# GPS_and_Telemetry.net
KiCad netlist of a schematic drawn in Altium Designer
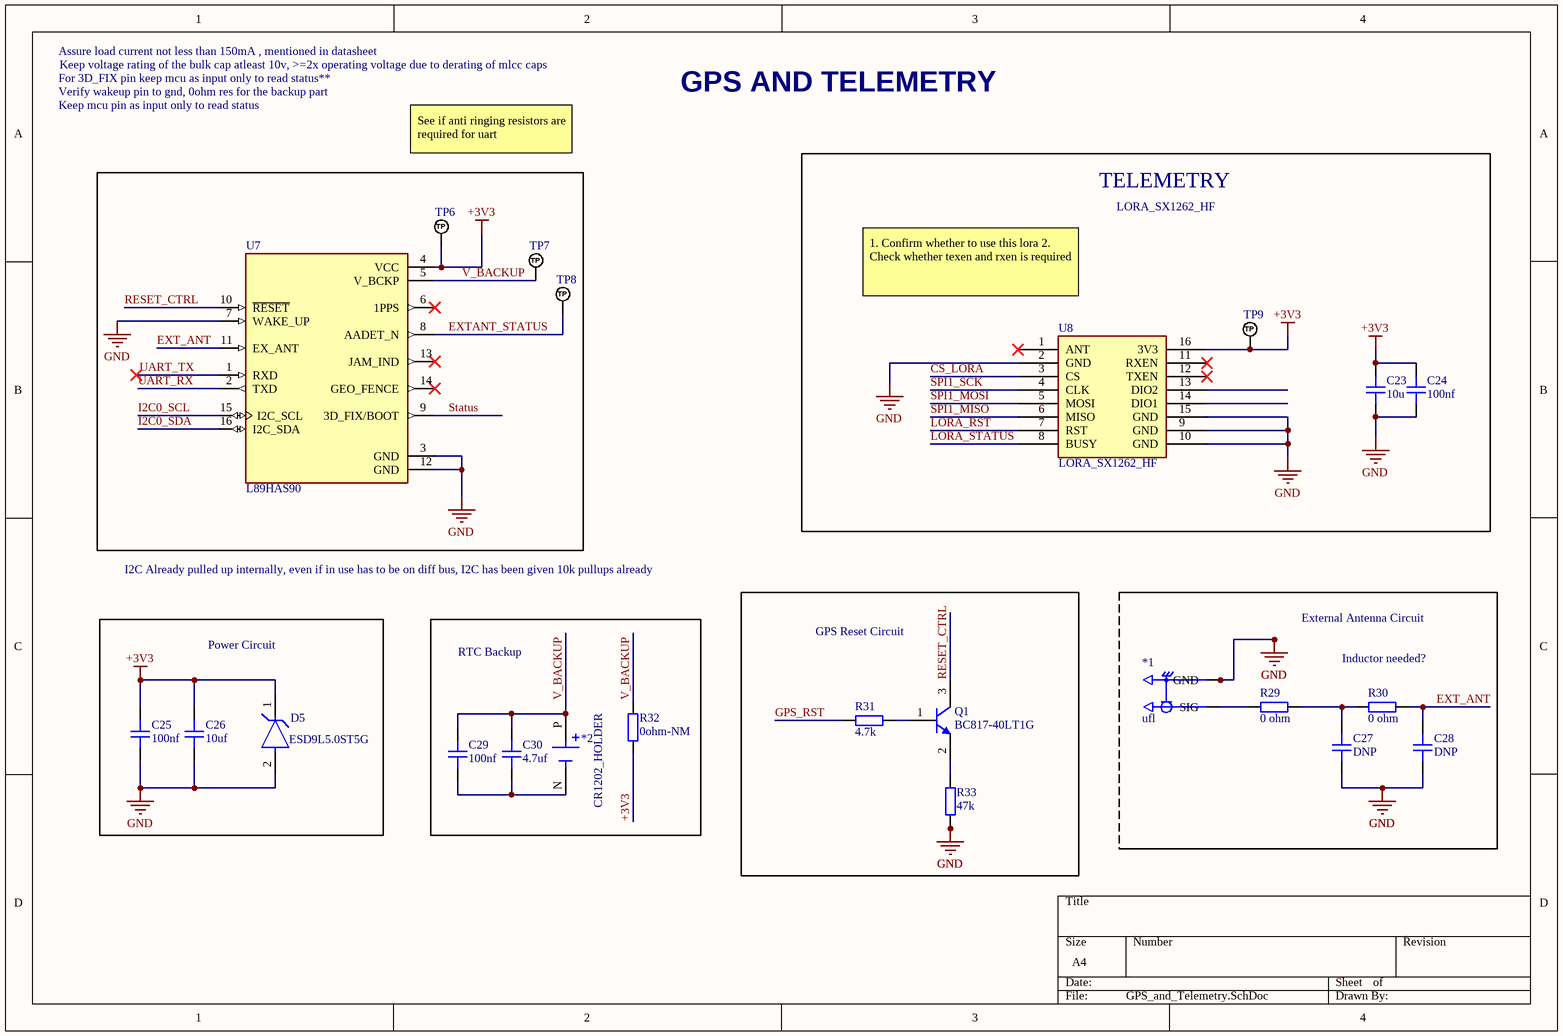
[diagram p0: GPS_and_Telemetry.SchDoc]

(export (version "E")
  (design (tool "Eeschema 10.0.6"))
  (components
    (comp (ref "*1") (value "ufl") (footprint "UFL") (libsource (lib "SchematicSchlib1") (part "ufl")))
    (comp (ref "*2")
      (value "CR1202_HOLDER")
      (footprint "CR1220_CELL_HOLDER")
      (libsource (lib "SchematicSchlib1") (part "CR1202_HOLDER"))
    )
    (comp (ref "C23")
      (value "10u")
      (footprint "CAP_0805")
      (description "Capacitor SMD 0805")
      (libsource (lib "SchematicSchlib1") (part "CAP_0805"))
    )
    (comp (ref "C24")
      (value "100nf")
      (footprint "CAP_0402")
      (description "Capacitor SMD 0402")
      (libsource (lib "SchematicSchlib1") (part "CAP_0402"))
    )
    (comp (ref "C25")
      (value "100nf")
      (footprint "CAP_0402")
      (description "Capacitor SMD 0402")
      (libsource (lib "SchematicSchlib1") (part "CAP_0402"))
    )
    (comp (ref "C26")
      (value "10uf")
      (footprint "CAP_0805")
      (description "Capacitor SMD 0805")
      (libsource (lib "SchematicSchlib1") (part "CAP_0805"))
    )
    (comp (ref "C27")
      (value "DNP")
      (footprint "CAP_0402")
      (description "Capacitor SMD 0402")
      (libsource (lib "SchematicSchlib1") (part "CAP_0402"))
    )
    (comp (ref "C28")
      (value "DNP")
      (footprint "CAP_0402")
      (description "Capacitor SMD 0402")
      (libsource (lib "SchematicSchlib1") (part "CAP_0402"))
    )
    (comp (ref "C29")
      (value "100nf")
      (footprint "CAP_0402")
      (description "Capacitor SMD 0402")
      (libsource (lib "SchematicSchlib1") (part "CAP_0402"))
    )
    (comp (ref "C30")
      (value "4.7uf")
      (footprint "CAP_0805")
      (description "Capacitor SMD 0805")
      (libsource (lib "SchematicSchlib1") (part "CAP_0805"))
    )
    (comp (ref "D5")
      (value "ESD9L5.0ST5G")
      (footprint "On_Semiconductor_514AB_MFG")
      (libsource (lib "Altium Content Vault") (part "ESD9L5_0ST5G"))
    )
    (comp (ref "Q1")
      (value "BC817-40LT1G")
      (footprint "ONSC-SOT-23-3-318-08_V")
      (description "General Purpose Transistor, NPN Silicon, 3-Pin SOT-23, Pb-Free, Tape and Reel")
      (fields (field (name "MANUFACTURER") "On Semiconductor"))
      (libsource (lib "Altium Content Vault") (part "ONSC-NPN-B1E2C3-3"))
    )
    (comp (ref "R29")
      (value "0 ohm")
      (footprint "RES_0402")
      (description "Resistor SMD 0402")
      (libsource (lib "SchematicSchlib1") (part "RES_0402"))
    )
    (comp (ref "R30")
      (value "0 ohm")
      (footprint "RES_0402")
      (description "Resistor SMD 0402")
      (libsource (lib "SchematicSchlib1") (part "RES_0402"))
    )
    (comp (ref "R31")
      (value "4.7k")
      (footprint "RES_0402")
      (description "Resistor SMD 0402")
      (libsource (lib "SchematicSchlib1") (part "RES_0402"))
    )
    (comp (ref "R32")
      (value "0ohm-NM")
      (footprint "RES_0603")
      (description "Resistor SMD 0603")
      (libsource (lib "SchematicSchlib1") (part "RES_0603"))
    )
    (comp (ref "R33")
      (value "47k")
      (footprint "RES_0402")
      (description "Resistor SMD 0402")
      (libsource (lib "SchematicSchlib1") (part "RES_0402"))
    )
    (comp (ref "TP6")
      (value "TEST_POINT_RND_1MM")
      (footprint "PAD_RND_1MM")
      (description "Test Point Round 1mm (NO BOM)")
      (fields (field (name "SOURCE") "Schematic-Lib-PhilsLab.SchLib"))
      (libsource (lib "Shravan Talapady") (part "TEST_POINT_RND_1MM"))
    )
    (comp (ref "TP7")
      (value "TEST_POINT_RND_1MM")
      (footprint "PAD_RND_1MM")
      (description "Test Point Round 1mm (NO BOM)")
      (fields (field (name "SOURCE") "Schematic-Lib-PhilsLab.SchLib"))
      (libsource (lib "Shravan Talapady") (part "TEST_POINT_RND_1MM"))
    )
    (comp (ref "TP8")
      (value "TEST_POINT_RND_1MM")
      (footprint "PAD_RND_1MM")
      (description "Test Point Round 1mm (NO BOM)")
      (fields (field (name "SOURCE") "Schematic-Lib-PhilsLab.SchLib"))
      (libsource (lib "Shravan Talapady") (part "TEST_POINT_RND_1MM"))
    )
    (comp (ref "TP9")
      (value "TEST_POINT_RND_1MM")
      (footprint "PAD_RND_1MM")
      (description "Test Point Round 1mm (NO BOM)")
      (fields (field (name "SOURCE") "Schematic-Lib-PhilsLab.SchLib"))
      (libsource (lib "Shravan Talapady") (part "TEST_POINT_RND_1MM"))
    )
    (comp (ref "U7")
      (value "L89HAS90")
      (footprint "AvionicsPcbLib1:XCVR_L89HAS90")
      (fields (field (name "MF") "Quectel") (field (name "DIGI-KEY_PART_NUMBER") "2958-L89HA-S90TR-ND"))
      (libsource (lib "SchematicSchlib1") (part "L89HAS90"))
    )
    (comp (ref "U8")
      (value "LORA_SX1262_HF")
      (footprint "LORA_SX1262_HF")
      (libsource (lib "SchematicSchlib1") (part "LORA_SX1262_HF"))
    )
  )
  (nets
    (net (code "1") (name "+3V3") (class "Default")
      (node (ref "C23") (pin "2") (pinfunction "2_2") (pintype "passive"))
      (node (ref "C24") (pin "2") (pinfunction "2_2") (pintype "passive"))
      (node (ref "C25") (pin "2") (pinfunction "2_2") (pintype "passive"))
      (node (ref "C26") (pin "2") (pinfunction "2_2") (pintype "passive"))
      (node (ref "D5") (pin "1") (pinfunction "C_1") (pintype "passive"))
      (node (ref "R32") (pin "1") (pinfunction "1_1") (pintype "passive"))
      (node (ref "TP6") (pin "1") (pinfunction "TP_1") (pintype "passive"))
      (node (ref "TP9") (pin "1") (pinfunction "TP_1") (pintype "passive"))
      (node (ref "U7") (pin "4") (pinfunction "VCC_4") (pintype "power_in"))
      (node (ref "U8") (pin "16") (pinfunction "3V3_16") (pintype "passive"))
    )
    (net (code "2") (name "/CS_LORA") (class "Default")
      (node (ref "U8") (pin "3") (pinfunction "CS_3") (pintype "passive"))
    )
    (net (code "3") (name "/EXTANT_STATUS") (class "Default")
      (node (ref "TP8") (pin "1") (pinfunction "TP_1") (pintype "passive"))
      (node (ref "U7") (pin "8") (pinfunction "AADET_N_8") (pintype "output"))
    )
    (net (code "4") (name "/EXT_ANT") (class "Default")
      (node (ref "C28") (pin "2") (pinfunction "2_2") (pintype "passive"))
      (node (ref "R30") (pin "2") (pinfunction "2_2") (pintype "passive"))
      (node (ref "U7") (pin "11") (pinfunction "EX_ANT_11") (pintype "input"))
    )
    (net (code "5") (name "/GPS_RST") (class "Default")
      (node (ref "R31") (pin "1") (pinfunction "1_1") (pintype "passive"))
    )
    (net (code "6") (name "/I2C0_SCL") (class "Default")
      (node (ref "U7") (pin "15") (pinfunction "I2C_SCL_15") (pintype "bidirectional"))
    )
    (net (code "7") (name "/I2C0_SDA") (class "Default")
      (node (ref "U7") (pin "16") (pinfunction "I2C_SDA_16") (pintype "bidirectional"))
    )
    (net (code "8") (name "/LORA_RST") (class "Default")
      (node (ref "U8") (pin "7") (pinfunction "RST_7") (pintype "passive"))
    )
    (net (code "9") (name "/LORA_STATUS") (class "Default")
      (node (ref "U8") (pin "8") (pinfunction "BUSY_8") (pintype "passive"))
    )
    (net (code "10") (name "/RESET_CTRL") (class "Default")
      (node (ref "Q1") (pin "3") (pinfunction "C_3") (pintype "passive"))
      (node (ref "U7") (pin "10") (pinfunction "~{RESET}_10") (pintype "input"))
    )
    (net (code "11") (name "/SPI1_MISO") (class "Default")
      (node (ref "U8") (pin "6") (pinfunction "MISO_6") (pintype "passive"))
    )
    (net (code "12") (name "/SPI1_MOSI") (class "Default")
      (node (ref "U8") (pin "5") (pinfunction "MOSI_5") (pintype "passive"))
    )
    (net (code "13") (name "/SPI1_SCK") (class "Default")
      (node (ref "U8") (pin "4") (pinfunction "CLK_4") (pintype "passive"))
    )
    (net (code "14") (name "/Status") (class "Default")
      (node (ref "U7") (pin "9") (pinfunction "3D_FIX/BOOT_9") (pintype "output"))
    )
    (net (code "15") (name "/UART_RX") (class "Default")
      (node (ref "U7") (pin "2") (pinfunction "TXD_2") (pintype "output"))
    )
    (net (code "16") (name "/UART_TX") (class "Default")
      (node (ref "U7") (pin "1") (pinfunction "RXD_1") (pintype "input+no_connect"))
    )
    (net (code "17") (name "/V_BACKUP") (class "Default")
      (node (ref "*2") (pin "P") (pinfunction "POS_P") (pintype "passive"))
      (node (ref "C29") (pin "2") (pinfunction "2_2") (pintype "passive"))
      (node (ref "C30") (pin "2") (pinfunction "2_2") (pintype "passive"))
      (node (ref "R32") (pin "2") (pinfunction "2_2") (pintype "passive"))
      (node (ref "TP7") (pin "1") (pinfunction "TP_1") (pintype "passive"))
      (node (ref "U7") (pin "5") (pinfunction "V_BCKP_5") (pintype "power_in"))
    )
    (net (code "18") (name "GND") (class "Default")
      (node (ref "*1") (pin "1") (pinfunction "GND_1") (pintype "passive"))
      (node (ref "*1") (pin "2") (pinfunction "GND_2") (pintype "passive"))
      (node (ref "C23") (pin "1") (pinfunction "1_1") (pintype "passive"))
      (node (ref "C24") (pin "1") (pinfunction "1_1") (pintype "passive"))
      (node (ref "C25") (pin "1") (pinfunction "1_1") (pintype "passive"))
      (node (ref "C26") (pin "1") (pinfunction "1_1") (pintype "passive"))
      (node (ref "C27") (pin "1") (pinfunction "1_1") (pintype "passive"))
      (node (ref "C28") (pin "1") (pinfunction "1_1") (pintype "passive"))
      (node (ref "D5") (pin "2") (pinfunction "A_2") (pintype "passive"))
      (node (ref "R33") (pin "1") (pinfunction "1_1") (pintype "passive"))
      (node (ref "U7") (pin "12") (pinfunction "GND_12") (pintype "power_in"))
      (node (ref "U7") (pin "3") (pinfunction "GND_3") (pintype "power_in"))
      (node (ref "U7") (pin "7") (pinfunction "WAKE_UP_7") (pintype "input"))
      (node (ref "U8") (pin "10") (pinfunction "GND_10") (pintype "passive"))
      (node (ref "U8") (pin "15") (pinfunction "GND_15") (pintype "passive"))
      (node (ref "U8") (pin "2") (pinfunction "GND_2") (pintype "passive"))
      (node (ref "U8") (pin "9") (pinfunction "GND_9") (pintype "passive"))
    )
    (net (code "19") (name "Net-(*1-SIG)") (class "Default")
      (node (ref "*1") (pin "3") (pinfunction "SIG_3") (pintype "passive"))
      (node (ref "R29") (pin "1") (pinfunction "1_1") (pintype "passive"))
    )
    (net (code "20") (name "Net-(*2-NEG)") (class "Default")
      (node (ref "*2") (pin "N") (pinfunction "NEG_N") (pintype "passive"))
      (node (ref "C29") (pin "1") (pinfunction "1_1") (pintype "passive"))
      (node (ref "C30") (pin "1") (pinfunction "1_1") (pintype "passive"))
    )
    (net (code "21") (name "Net-(C27-Pad2)") (class "Default")
      (node (ref "C27") (pin "2") (pinfunction "2_2") (pintype "passive"))
      (node (ref "R29") (pin "2") (pinfunction "2_2") (pintype "passive"))
      (node (ref "R30") (pin "1") (pinfunction "1_1") (pintype "passive"))
    )
    (net (code "22") (name "Net-(Q1-B)") (class "Default")
      (node (ref "Q1") (pin "1") (pinfunction "B_1") (pintype "passive"))
      (node (ref "R31") (pin "2") (pinfunction "2_2") (pintype "passive"))
    )
    (net (code "23") (name "Net-(Q1-E)") (class "Default")
      (node (ref "Q1") (pin "2") (pinfunction "E_2") (pintype "passive"))
      (node (ref "R33") (pin "2") (pinfunction "2_2") (pintype "passive"))
    )
    (net (code "24") (name "unconnected-(U7-1PPS-Pad6)") (class "Default")
      (node (ref "U7") (pin "6") (pinfunction "1PPS_6") (pintype "output+no_connect"))
    )
    (net (code "25") (name "unconnected-(U7-GEO_FENCE-Pad14)") (class "Default")
      (node (ref "U7") (pin "14") (pinfunction "GEO_FENCE_14") (pintype "output+no_connect"))
    )
    (net (code "26") (name "unconnected-(U7-JAM_IND-Pad13)") (class "Default")
      (node (ref "U7") (pin "13") (pinfunction "JAM_IND_13") (pintype "output+no_connect"))
    )
    (net (code "27") (name "unconnected-(U8-ANT-Pad1)") (class "Default")
      (node (ref "U8") (pin "1") (pinfunction "ANT_1") (pintype "passive+no_connect"))
    )
    (net (code "28") (name "unconnected-(U8-DIO1-Pad14)") (class "Default")
      (node (ref "U8") (pin "14") (pinfunction "DIO1_14") (pintype "passive"))
    )
    (net (code "29") (name "unconnected-(U8-DIO2-Pad13)") (class "Default")
      (node (ref "U8") (pin "13") (pinfunction "DIO2_13") (pintype "passive"))
    )
    (net (code "30") (name "unconnected-(U8-RXEN-Pad11)") (class "Default")
      (node (ref "U8") (pin "11") (pinfunction "RXEN_11") (pintype "passive+no_connect"))
    )
    (net (code "31") (name "unconnected-(U8-TXEN-Pad12)") (class "Default")
      (node (ref "U8") (pin "12") (pinfunction "TXEN_12") (pintype "passive+no_connect"))
    )
  )
)
